# test2235.net
KiCad netlist of a schematic drawn in Altium Designer
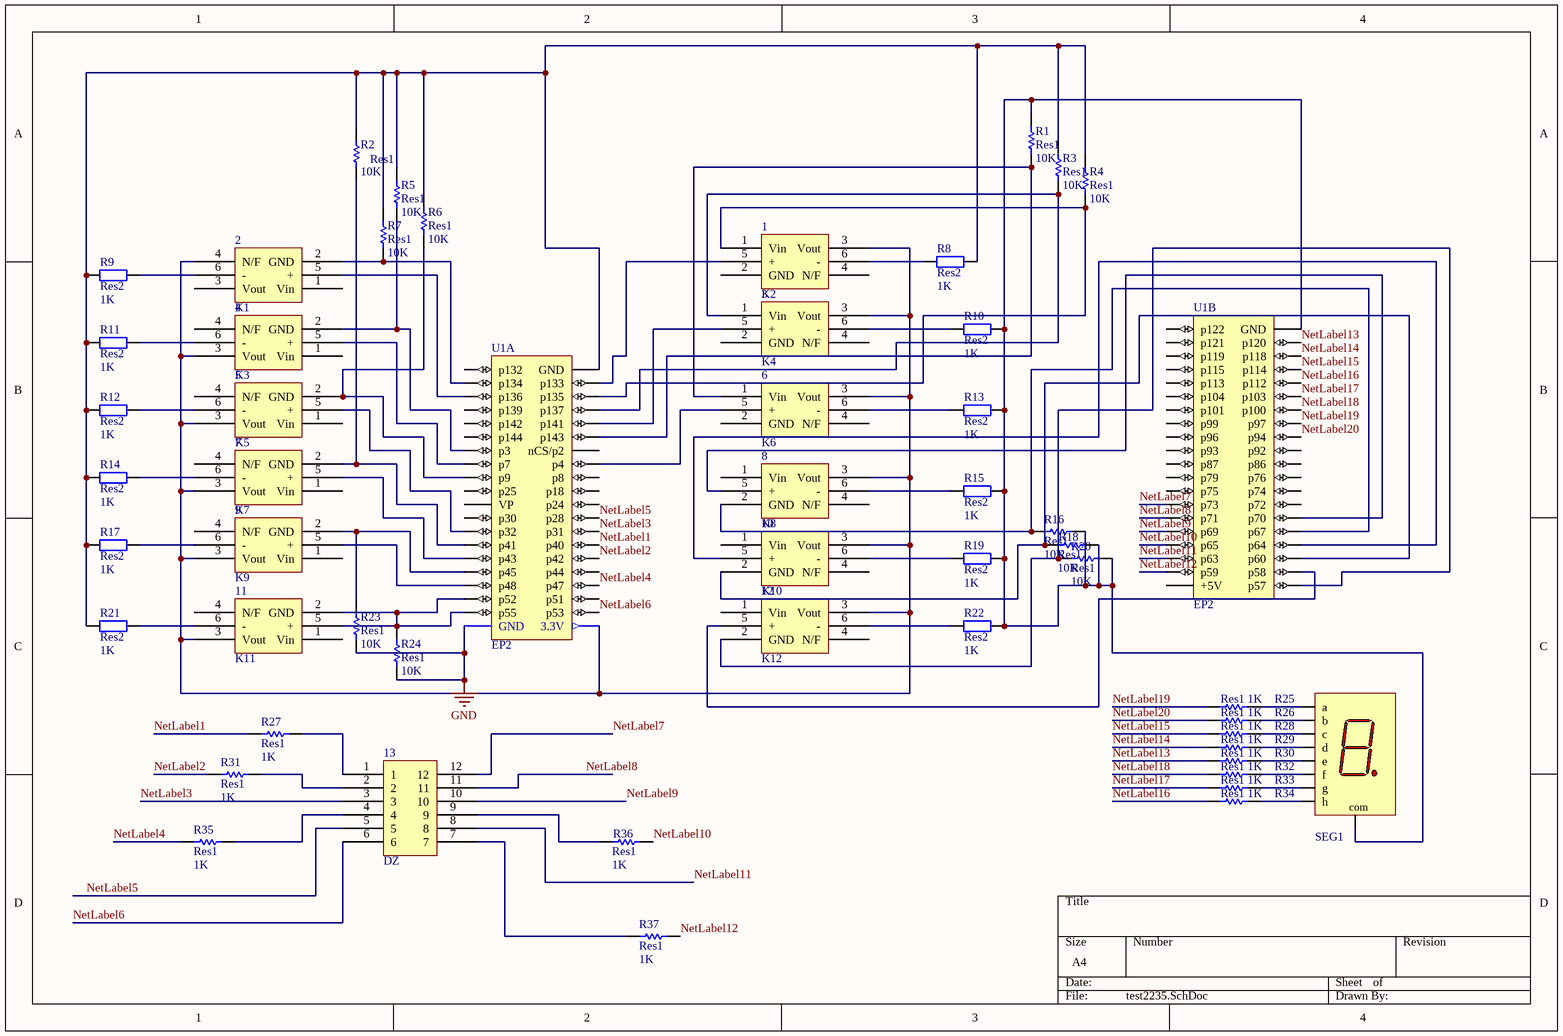
[diagram p0: test2235.SchDoc]

(export (version "E")
  (design (tool "Eeschema 10.0.6"))
  (components
    (comp (ref "1") (value "K2") (footprint "KG") (libsource (lib "KG1") (part "Component_1")))
    (comp (ref "2")
      (value "K1")
      (footprint "KG")
      (libsource (lib "Integrated_Library1") (part "Component_1"))
    )
    (comp (ref "3") (value "K4") (footprint "KG") (libsource (lib "KG1") (part "Component_1")))
    (comp (ref "4")
      (value "K3")
      (footprint "KG")
      (libsource (lib "Integrated_Library1") (part "Component_1"))
    )
    (comp (ref "5")
      (value "K5")
      (footprint "KG")
      (libsource (lib "Integrated_Library1") (part "Component_1"))
    )
    (comp (ref "6") (value "K6") (footprint "KG") (libsource (lib "KG1") (part "Component_1")))
    (comp (ref "7")
      (value "K7")
      (footprint "KG")
      (libsource (lib "Integrated_Library1") (part "Component_1"))
    )
    (comp (ref "8") (value "K8") (footprint "KG") (libsource (lib "KG1") (part "Component_1")))
    (comp (ref "9")
      (value "K9")
      (footprint "KG")
      (libsource (lib "Integrated_Library1") (part "Component_1"))
    )
    (comp (ref "10") (value "K10") (footprint "KG") (libsource (lib "KG1") (part "Component_1")))
    (comp (ref "11")
      (value "K11")
      (footprint "KG")
      (libsource (lib "Integrated_Library1") (part "Component_1"))
    )
    (comp (ref "12") (value "K12") (footprint "KG") (libsource (lib "KG1") (part "Component_1")))
    (comp (ref "13") (value "DZ") (footprint "DZ") (libsource (lib "DZ") (part "DZ")))
    (comp (ref "R1")
      (value "Res1")
      (footprint "AXIAL-0.3")
      (description "Resistor")
      (fields (field (name "ALTIUM_VALUE") "10K") (field (name "PUBLISHER") "Altium Limited"))
      (libsource (lib "Miscellaneous Devices") (part "Res1"))
    )
    (comp (ref "R2")
      (value "Res1")
      (footprint "AXIAL-0.3")
      (description "Resistor")
      (fields (field (name "ALTIUM_VALUE") "10K") (field (name "PUBLISHER") "Altium Limited"))
      (libsource (lib "Miscellaneous Devices") (part "Res1"))
    )
    (comp (ref "R3")
      (value "Res1")
      (footprint "AXIAL-0.3")
      (description "Resistor")
      (fields (field (name "ALTIUM_VALUE") "10K") (field (name "PUBLISHER") "Altium Limited"))
      (libsource (lib "Miscellaneous Devices") (part "Res1"))
    )
    (comp (ref "R4")
      (value "Res1")
      (footprint "AXIAL-0.3")
      (description "Resistor")
      (fields (field (name "ALTIUM_VALUE") "10K") (field (name "PUBLISHER") "Altium Limited"))
      (libsource (lib "Miscellaneous Devices") (part "Res1"))
    )
    (comp (ref "R5")
      (value "Res1")
      (footprint "AXIAL-0.3")
      (description "Resistor")
      (fields (field (name "ALTIUM_VALUE") "10K") (field (name "PUBLISHER") "Altium Limited"))
      (libsource (lib "Miscellaneous Devices") (part "Res1"))
    )
    (comp (ref "R6")
      (value "Res1")
      (footprint "AXIAL-0.3")
      (description "Resistor")
      (fields (field (name "ALTIUM_VALUE") "10K") (field (name "PUBLISHER") "Altium Limited"))
      (libsource (lib "Miscellaneous Devices") (part "Res1"))
    )
    (comp (ref "R7")
      (value "Res1")
      (footprint "AXIAL-0.3")
      (description "Resistor")
      (fields (field (name "ALTIUM_VALUE") "10K") (field (name "PUBLISHER") "Altium Limited"))
      (libsource (lib "Miscellaneous Devices") (part "Res1"))
    )
    (comp (ref "R8")
      (value "Res2")
      (footprint "AXIAL-0.4")
      (description "Resistor")
      (fields (field (name "ALTIUM_VALUE") "1K") (field (name "PUBLISHER") "Altium Limited"))
      (libsource (lib "Miscellaneous Devices") (part "Res2"))
    )
    (comp (ref "R9")
      (value "Res2")
      (footprint "AXIAL-0.4")
      (description "Resistor")
      (fields (field (name "ALTIUM_VALUE") "1K") (field (name "PUBLISHER") "Altium Limited"))
      (libsource (lib "Miscellaneous Devices") (part "Res2"))
    )
    (comp (ref "R10")
      (value "Res2")
      (footprint "AXIAL-0.4")
      (description "Resistor")
      (fields (field (name "ALTIUM_VALUE") "1K") (field (name "PUBLISHER") "Altium Limited"))
      (libsource (lib "Miscellaneous Devices") (part "Res2"))
    )
    (comp (ref "R11")
      (value "Res2")
      (footprint "AXIAL-0.4")
      (description "Resistor")
      (fields (field (name "ALTIUM_VALUE") "1K") (field (name "PUBLISHER") "Altium Limited"))
      (libsource (lib "Miscellaneous Devices") (part "Res2"))
    )
    (comp (ref "R12")
      (value "Res2")
      (footprint "AXIAL-0.4")
      (description "Resistor")
      (fields (field (name "ALTIUM_VALUE") "1K") (field (name "PUBLISHER") "Altium Limited"))
      (libsource (lib "Miscellaneous Devices") (part "Res2"))
    )
    (comp (ref "R13")
      (value "Res2")
      (footprint "AXIAL-0.4")
      (description "Resistor")
      (fields (field (name "ALTIUM_VALUE") "1K") (field (name "PUBLISHER") "Altium Limited"))
      (libsource (lib "Miscellaneous Devices") (part "Res2"))
    )
    (comp (ref "R14")
      (value "Res2")
      (footprint "AXIAL-0.4")
      (description "Resistor")
      (fields (field (name "ALTIUM_VALUE") "1K") (field (name "PUBLISHER") "Altium Limited"))
      (libsource (lib "Miscellaneous Devices") (part "Res2"))
    )
    (comp (ref "R15")
      (value "Res2")
      (footprint "AXIAL-0.4")
      (description "Resistor")
      (fields (field (name "ALTIUM_VALUE") "1K") (field (name "PUBLISHER") "Altium Limited"))
      (libsource (lib "Miscellaneous Devices") (part "Res2"))
    )
    (comp (ref "R16")
      (value "Res1")
      (footprint "AXIAL-0.3")
      (description "Resistor")
      (fields (field (name "ALTIUM_VALUE") "10K") (field (name "PUBLISHER") "Altium Limited"))
      (libsource (lib "Miscellaneous Devices") (part "Res1"))
    )
    (comp (ref "R17")
      (value "Res2")
      (footprint "AXIAL-0.4")
      (description "Resistor")
      (fields (field (name "ALTIUM_VALUE") "1K") (field (name "PUBLISHER") "Altium Limited"))
      (libsource (lib "Miscellaneous Devices") (part "Res2"))
    )
    (comp (ref "R18")
      (value "Res1")
      (footprint "AXIAL-0.3")
      (description "Resistor")
      (fields (field (name "ALTIUM_VALUE") "10K") (field (name "PUBLISHER") "Altium Limited"))
      (libsource (lib "Miscellaneous Devices") (part "Res1"))
    )
    (comp (ref "R19")
      (value "Res2")
      (footprint "AXIAL-0.4")
      (description "Resistor")
      (fields (field (name "ALTIUM_VALUE") "1K") (field (name "PUBLISHER") "Altium Limited"))
      (libsource (lib "Miscellaneous Devices") (part "Res2"))
    )
    (comp (ref "R20")
      (value "Res1")
      (footprint "AXIAL-0.3")
      (description "Resistor")
      (fields (field (name "ALTIUM_VALUE") "10K") (field (name "PUBLISHER") "Altium Limited"))
      (libsource (lib "Miscellaneous Devices") (part "Res1"))
    )
    (comp (ref "R21")
      (value "Res2")
      (footprint "AXIAL-0.4")
      (description "Resistor")
      (fields (field (name "ALTIUM_VALUE") "1K") (field (name "PUBLISHER") "Altium Limited"))
      (libsource (lib "Miscellaneous Devices") (part "Res2"))
    )
    (comp (ref "R22")
      (value "Res2")
      (footprint "AXIAL-0.4")
      (description "Resistor")
      (fields (field (name "ALTIUM_VALUE") "1K") (field (name "PUBLISHER") "Altium Limited"))
      (libsource (lib "Miscellaneous Devices") (part "Res2"))
    )
    (comp (ref "R23")
      (value "Res1")
      (footprint "AXIAL-0.3")
      (description "Resistor")
      (fields (field (name "ALTIUM_VALUE") "10K") (field (name "PUBLISHER") "Altium Limited"))
      (libsource (lib "Miscellaneous Devices") (part "Res1"))
    )
    (comp (ref "R24")
      (value "Res1")
      (footprint "AXIAL-0.3")
      (description "Resistor")
      (fields (field (name "ALTIUM_VALUE") "10K") (field (name "PUBLISHER") "Altium Limited"))
      (libsource (lib "Miscellaneous Devices") (part "Res1"))
    )
    (comp (ref "R25")
      (value "Res1")
      (footprint "AXIAL-0.3")
      (description "Resistor")
      (fields (field (name "ALTIUM_VALUE") "1K") (field (name "PUBLISHER") "Altium Limited"))
      (libsource (lib "Miscellaneous Devices") (part "Res1"))
    )
    (comp (ref "R26")
      (value "Res1")
      (footprint "AXIAL-0.3")
      (description "Resistor")
      (fields (field (name "ALTIUM_VALUE") "1K") (field (name "PUBLISHER") "Altium Limited"))
      (libsource (lib "Miscellaneous Devices") (part "Res1"))
    )
    (comp (ref "R27")
      (value "Res1")
      (footprint "AXIAL-0.3")
      (description "Resistor")
      (fields (field (name "ALTIUM_VALUE") "1K") (field (name "PUBLISHER") "Altium Limited"))
      (libsource (lib "Miscellaneous Devices") (part "Res1"))
    )
    (comp (ref "R28")
      (value "Res1")
      (footprint "AXIAL-0.3")
      (description "Resistor")
      (fields (field (name "ALTIUM_VALUE") "1K") (field (name "PUBLISHER") "Altium Limited"))
      (libsource (lib "Miscellaneous Devices") (part "Res1"))
    )
    (comp (ref "R29")
      (value "Res1")
      (footprint "AXIAL-0.3")
      (description "Resistor")
      (fields (field (name "ALTIUM_VALUE") "1K") (field (name "PUBLISHER") "Altium Limited"))
      (libsource (lib "Miscellaneous Devices") (part "Res1"))
    )
    (comp (ref "R30")
      (value "Res1")
      (footprint "AXIAL-0.3")
      (description "Resistor")
      (fields (field (name "ALTIUM_VALUE") "1K") (field (name "PUBLISHER") "Altium Limited"))
      (libsource (lib "Miscellaneous Devices") (part "Res1"))
    )
    (comp (ref "R31")
      (value "Res1")
      (footprint "AXIAL-0.3")
      (description "Resistor")
      (fields (field (name "ALTIUM_VALUE") "1K") (field (name "PUBLISHER") "Altium Limited"))
      (libsource (lib "Miscellaneous Devices") (part "Res1"))
    )
    (comp (ref "R32")
      (value "Res1")
      (footprint "AXIAL-0.3")
      (description "Resistor")
      (fields (field (name "ALTIUM_VALUE") "1K") (field (name "PUBLISHER") "Altium Limited"))
      (libsource (lib "Miscellaneous Devices") (part "Res1"))
    )
    (comp (ref "R33")
      (value "Res1")
      (footprint "AXIAL-0.3")
      (description "Resistor")
      (fields (field (name "ALTIUM_VALUE") "1K") (field (name "PUBLISHER") "Altium Limited"))
      (libsource (lib "Miscellaneous Devices") (part "Res1"))
    )
    (comp (ref "R34")
      (value "Res1")
      (footprint "AXIAL-0.3")
      (description "Resistor")
      (fields (field (name "ALTIUM_VALUE") "1K") (field (name "PUBLISHER") "Altium Limited"))
      (libsource (lib "Miscellaneous Devices") (part "Res1"))
    )
    (comp (ref "R35")
      (value "Res1")
      (footprint "AXIAL-0.3")
      (description "Resistor")
      (fields (field (name "ALTIUM_VALUE") "1K") (field (name "PUBLISHER") "Altium Limited"))
      (libsource (lib "Miscellaneous Devices") (part "Res1"))
    )
    (comp (ref "R36")
      (value "Res1")
      (footprint "AXIAL-0.3")
      (description "Resistor")
      (fields (field (name "ALTIUM_VALUE") "1K") (field (name "PUBLISHER") "Altium Limited"))
      (libsource (lib "Miscellaneous Devices") (part "Res1"))
    )
    (comp (ref "R37")
      (value "Res1")
      (footprint "AXIAL-0.3")
      (description "Resistor")
      (fields (field (name "ALTIUM_VALUE") "1K") (field (name "PUBLISHER") "Altium Limited"))
      (libsource (lib "Miscellaneous Devices") (part "Res1"))
    )
    (comp (ref "SEG1")
      (value "Displayer-SEG-7")
      (footprint "lanfengdi:QH5011AS")
      (description "七段数码管")
      (libsource (lib "lanfengdi") (part "Displayer-SEG-7"))
    )
    (comp (ref "U1")
      (value "EP2")
      (footprint "lanfengdi:EP2-TQFP144")
      (description "适用于连接西南交大电子学实验室的MFB5上用的FPGA小板")
      (libsource (lib "lanfengdi") (part "EP2"))
    )
  )
  (nets
    (net (code "1") (name "/NetLabel1") (class "Default")
      (node (ref "R27") (pin "2") (pinfunction "2_2") (pintype "passive"))
      (node (ref "U1") (pin "25") (pinfunction "p40_25") (pintype "bidirectional"))
    )
    (net (code "2") (name "/NetLabel2") (class "Default")
      (node (ref "R31") (pin "2") (pinfunction "2_2") (pintype "passive"))
      (node (ref "U1") (pin "24") (pinfunction "p42_24") (pintype "bidirectional"))
    )
    (net (code "3") (name "/NetLabel3") (class "Default")
      (node (ref "13") (pin "3") (pinfunction "3_3") (pintype "passive"))
      (node (ref "U1") (pin "26") (pinfunction "p31_26") (pintype "bidirectional"))
    )
    (net (code "4") (name "/NetLabel4") (class "Default")
      (node (ref "R35") (pin "2") (pinfunction "2_2") (pintype "passive"))
      (node (ref "U1") (pin "22") (pinfunction "p47_22") (pintype "bidirectional"))
    )
    (net (code "5") (name "/NetLabel5") (class "Default")
      (node (ref "13") (pin "5") (pinfunction "5_5") (pintype "passive"))
      (node (ref "U1") (pin "27") (pinfunction "p28_27") (pintype "bidirectional"))
    )
    (net (code "6") (name "/NetLabel6") (class "Default")
      (node (ref "13") (pin "6") (pinfunction "6_6") (pintype "passive"))
      (node (ref "U1") (pin "20") (pinfunction "p53_20") (pintype "bidirectional"))
    )
    (net (code "7") (name "/NetLabel7") (class "Default")
      (node (ref "13") (pin "12") (pinfunction "12_12") (pintype "passive"))
      (node (ref "U1") (pin "52") (pinfunction "p73_52") (pintype "bidirectional"))
    )
    (net (code "8") (name "/NetLabel8") (class "Default")
      (node (ref "13") (pin "11") (pinfunction "11_11") (pintype "passive"))
      (node (ref "U1") (pin "53") (pinfunction "p71_53") (pintype "bidirectional"))
    )
    (net (code "9") (name "/NetLabel9") (class "Default")
      (node (ref "13") (pin "10") (pinfunction "10_10") (pintype "passive"))
      (node (ref "U1") (pin "54") (pinfunction "p69_54") (pintype "bidirectional"))
    )
    (net (code "10") (name "/NetLabel10") (class "Default")
      (node (ref "R36") (pin "1") (pinfunction "1_1") (pintype "passive"))
      (node (ref "U1") (pin "55") (pinfunction "p65_55") (pintype "bidirectional"))
    )
    (net (code "11") (name "/NetLabel11") (class "Default")
      (node (ref "13") (pin "8") (pinfunction "8_8") (pintype "passive"))
      (node (ref "U1") (pin "56") (pinfunction "p63_56") (pintype "bidirectional"))
    )
    (net (code "12") (name "/NetLabel12") (class "Default")
      (node (ref "R37") (pin "1") (pinfunction "1_1") (pintype "passive"))
      (node (ref "U1") (pin "57") (pinfunction "p59_57") (pintype "bidirectional"))
    )
    (net (code "13") (name "/NetLabel13") (class "Default")
      (node (ref "R30") (pin "1") (pinfunction "1_1") (pintype "passive"))
      (node (ref "U1") (pin "77") (pinfunction "p120_77") (pintype "bidirectional"))
    )
    (net (code "14") (name "/NetLabel14") (class "Default")
      (node (ref "R29") (pin "1") (pinfunction "1_1") (pintype "passive"))
      (node (ref "U1") (pin "76") (pinfunction "p118_76") (pintype "bidirectional"))
    )
    (net (code "15") (name "/NetLabel15") (class "Default")
      (node (ref "R28") (pin "1") (pinfunction "1_1") (pintype "passive"))
      (node (ref "U1") (pin "75") (pinfunction "p114_75") (pintype "bidirectional"))
    )
    (net (code "16") (name "/NetLabel16") (class "Default")
      (node (ref "R34") (pin "1") (pinfunction "1_1") (pintype "passive"))
      (node (ref "U1") (pin "74") (pinfunction "p112_74") (pintype "bidirectional"))
    )
    (net (code "17") (name "/NetLabel17") (class "Default")
      (node (ref "R33") (pin "1") (pinfunction "1_1") (pintype "passive"))
      (node (ref "U1") (pin "73") (pinfunction "p103_73") (pintype "bidirectional"))
    )
    (net (code "18") (name "/NetLabel18") (class "Default")
      (node (ref "R32") (pin "1") (pinfunction "1_1") (pintype "passive"))
      (node (ref "U1") (pin "72") (pinfunction "p100_72") (pintype "bidirectional"))
    )
    (net (code "19") (name "/NetLabel19") (class "Default")
      (node (ref "R25") (pin "1") (pinfunction "1_1") (pintype "passive"))
      (node (ref "U1") (pin "71") (pinfunction "p97_71") (pintype "bidirectional"))
    )
    (net (code "20") (name "/NetLabel20") (class "Default")
      (node (ref "R26") (pin "1") (pinfunction "1_1") (pintype "passive"))
      (node (ref "U1") (pin "70") (pinfunction "p94_70") (pintype "bidirectional"))
    )
    (net (code "21") (name "GND") (class "Default")
      (node (ref "R23") (pin "1") (pinfunction "1_1") (pintype "passive"))
      (node (ref "R24") (pin "1") (pinfunction "1_1") (pintype "passive"))
      (node (ref "U1") (pin "79") (pinfunction "GND_79") (pintype "power_in"))
    )
    (net (code "22") (name "Net-(1-+)") (class "Default")
      (node (ref "1") (pin "5") (pinfunction "+_5") (pintype "passive"))
      (node (ref "U1") (pin "37") (pinfunction "p133_37") (pintype "bidirectional"))
    )
    (net (code "23") (name "Net-(1--)") (class "Default")
      (node (ref "1") (pin "6") (pinfunction "-_6") (pintype "passive"))
      (node (ref "R8") (pin "1") (pinfunction "1_1") (pintype "passive"))
    )
    (net (code "24") (name "Net-(1-Vin)") (class "Default")
      (node (ref "1") (pin "1") (pinfunction "Vin_1") (pintype "passive"))
      (node (ref "R4") (pin "1") (pinfunction "1_1") (pintype "passive"))
      (node (ref "U1") (pin "36") (pinfunction "p135_36") (pintype "bidirectional"))
    )
    (net (code "25") (name "Net-(1-Vout)") (class "Default")
      (node (ref "1") (pin "3") (pinfunction "Vout_3") (pintype "passive"))
      (node (ref "10") (pin "3") (pinfunction "Vout_3") (pintype "passive"))
      (node (ref "11") (pin "3") (pinfunction "Vout_3") (pintype "passive"))
      (node (ref "12") (pin "3") (pinfunction "Vout_3") (pintype "passive"))
      (node (ref "2") (pin "4") (pinfunction "N/F_4") (pintype "passive"))
      (node (ref "3") (pin "3") (pinfunction "Vout_3") (pintype "passive"))
      (node (ref "4") (pin "3") (pinfunction "Vout_3") (pintype "passive"))
      (node (ref "5") (pin "3") (pinfunction "Vout_3") (pintype "passive"))
      (node (ref "6") (pin "3") (pinfunction "Vout_3") (pintype "passive"))
      (node (ref "7") (pin "3") (pinfunction "Vout_3") (pintype "passive"))
      (node (ref "8") (pin "3") (pinfunction "Vout_3") (pintype "passive"))
      (node (ref "9") (pin "3") (pinfunction "Vout_3") (pintype "passive"))
      (node (ref "U1") (pin "80") (pinfunction "3.3V_80") (pintype "output"))
    )
    (net (code "26") (name "Net-(2-+)") (class "Default")
      (node (ref "2") (pin "5") (pinfunction "+_5") (pintype "passive"))
      (node (ref "U1") (pin "3") (pinfunction "p136_3") (pintype "bidirectional"))
    )
    (net (code "27") (name "Net-(2--)") (class "Default")
      (node (ref "2") (pin "6") (pinfunction "-_6") (pintype "passive"))
      (node (ref "R9") (pin "2") (pinfunction "2_2") (pintype "passive"))
    )
    (net (code "28") (name "Net-(2-GND)") (class "Default")
      (node (ref "2") (pin "2") (pinfunction "GND_2") (pintype "passive"))
      (node (ref "R7") (pin "1") (pinfunction "1_1") (pintype "passive"))
      (node (ref "U1") (pin "2") (pinfunction "p134_2") (pintype "bidirectional"))
    )
    (net (code "29") (name "Net-(3-+)") (class "Default")
      (node (ref "3") (pin "5") (pinfunction "+_5") (pintype "passive"))
      (node (ref "U1") (pin "34") (pinfunction "p141_34") (pintype "bidirectional"))
    )
    (net (code "30") (name "Net-(3--)") (class "Default")
      (node (ref "3") (pin "6") (pinfunction "-_6") (pintype "passive"))
      (node (ref "R10") (pin "1") (pinfunction "1_1") (pintype "passive"))
    )
    (net (code "31") (name "Net-(3-Vin)") (class "Default")
      (node (ref "3") (pin "1") (pinfunction "Vin_1") (pintype "passive"))
      (node (ref "R3") (pin "1") (pinfunction "1_1") (pintype "passive"))
      (node (ref "U1") (pin "35") (pinfunction "p137_35") (pintype "bidirectional"))
    )
    (net (code "32") (name "Net-(4-+)") (class "Default")
      (node (ref "4") (pin "5") (pinfunction "+_5") (pintype "passive"))
      (node (ref "U1") (pin "8") (pinfunction "p7_8") (pintype "bidirectional"))
    )
    (net (code "33") (name "Net-(4--)") (class "Default")
      (node (ref "4") (pin "6") (pinfunction "-_6") (pintype "passive"))
      (node (ref "R11") (pin "2") (pinfunction "2_2") (pintype "passive"))
    )
    (net (code "34") (name "Net-(4-GND)") (class "Default")
      (node (ref "4") (pin "2") (pinfunction "GND_2") (pintype "passive"))
      (node (ref "R5") (pin "1") (pinfunction "1_1") (pintype "passive"))
      (node (ref "U1") (pin "7") (pinfunction "p3_7") (pintype "bidirectional"))
    )
    (net (code "35") (name "Net-(5-+)") (class "Default")
      (node (ref "5") (pin "5") (pinfunction "+_5") (pintype "passive"))
      (node (ref "U1") (pin "13") (pinfunction "p32_13") (pintype "bidirectional"))
    )
    (net (code "36") (name "Net-(5--)") (class "Default")
      (node (ref "5") (pin "6") (pinfunction "-_6") (pintype "passive"))
      (node (ref "R12") (pin "2") (pinfunction "2_2") (pintype "passive"))
    )
    (net (code "37") (name "Net-(5-GND)") (class "Default")
      (node (ref "5") (pin "2") (pinfunction "GND_2") (pintype "passive"))
      (node (ref "R6") (pin "1") (pinfunction "1_1") (pintype "passive"))
      (node (ref "U1") (pin "9") (pinfunction "p9_9") (pintype "bidirectional"))
    )
    (net (code "38") (name "Net-(6-+)") (class "Default")
      (node (ref "6") (pin "5") (pinfunction "+_5") (pintype "passive"))
      (node (ref "U1") (pin "31") (pinfunction "p4_31") (pintype "bidirectional"))
    )
    (net (code "39") (name "Net-(6--)") (class "Default")
      (node (ref "6") (pin "6") (pinfunction "-_6") (pintype "passive"))
      (node (ref "R13") (pin "1") (pinfunction "1_1") (pintype "passive"))
    )
    (net (code "40") (name "Net-(6-Vin)") (class "Default")
      (node (ref "6") (pin "1") (pinfunction "Vin_1") (pintype "passive"))
      (node (ref "R1") (pin "1") (pinfunction "1_1") (pintype "passive"))
      (node (ref "U1") (pin "33") (pinfunction "p143_33") (pintype "bidirectional"))
    )
    (net (code "41") (name "Net-(7-+)") (class "Default")
      (node (ref "7") (pin "5") (pinfunction "+_5") (pintype "passive"))
      (node (ref "U1") (pin "15") (pinfunction "p43_15") (pintype "bidirectional"))
    )
    (net (code "42") (name "Net-(7--)") (class "Default")
      (node (ref "7") (pin "6") (pinfunction "-_6") (pintype "passive"))
      (node (ref "R14") (pin "2") (pinfunction "2_2") (pintype "passive"))
    )
    (net (code "43") (name "Net-(7-GND)") (class "Default")
      (node (ref "7") (pin "2") (pinfunction "GND_2") (pintype "passive"))
      (node (ref "R2") (pin "1") (pinfunction "1_1") (pintype "passive"))
      (node (ref "U1") (pin "14") (pinfunction "p41_14") (pintype "bidirectional"))
    )
    (net (code "44") (name "Net-(8-+)") (class "Default")
      (node (ref "8") (pin "5") (pinfunction "+_5") (pintype "passive"))
      (node (ref "U1") (pin "64") (pinfunction "p70_64") (pintype "bidirectional"))
    )
    (net (code "45") (name "Net-(8--)") (class "Default")
      (node (ref "8") (pin "6") (pinfunction "-_6") (pintype "passive"))
      (node (ref "R15") (pin "1") (pinfunction "1_1") (pintype "passive"))
    )
    (net (code "46") (name "Net-(8-GND)") (class "Default")
      (node (ref "8") (pin "2") (pinfunction "GND_2") (pintype "passive"))
      (node (ref "R16") (pin "1") (pinfunction "1_1") (pintype "passive"))
      (node (ref "U1") (pin "63") (pinfunction "p67_63") (pintype "bidirectional"))
    )
    (net (code "47") (name "Net-(9-+)") (class "Default")
      (node (ref "9") (pin "5") (pinfunction "+_5") (pintype "passive"))
      (node (ref "U1") (pin "17") (pinfunction "p48_17") (pintype "bidirectional"))
    )
    (net (code "48") (name "Net-(9--)") (class "Default")
      (node (ref "9") (pin "6") (pinfunction "-_6") (pintype "passive"))
      (node (ref "R17") (pin "2") (pinfunction "2_2") (pintype "passive"))
    )
    (net (code "49") (name "Net-(9-GND)") (class "Default")
      (node (ref "9") (pin "2") (pinfunction "GND_2") (pintype "passive"))
      (node (ref "R23") (pin "2") (pinfunction "2_2") (pintype "passive"))
      (node (ref "U1") (pin "16") (pinfunction "p45_16") (pintype "bidirectional"))
    )
    (net (code "50") (name "Net-(10-+)") (class "Default")
      (node (ref "10") (pin "5") (pinfunction "+_5") (pintype "passive"))
      (node (ref "U1") (pin "62") (pinfunction "p64_62") (pintype "bidirectional"))
    )
    (net (code "51") (name "Net-(10--)") (class "Default")
      (node (ref "10") (pin "6") (pinfunction "-_6") (pintype "passive"))
      (node (ref "R19") (pin "1") (pinfunction "1_1") (pintype "passive"))
    )
    (net (code "52") (name "Net-(10-GND)") (class "Default")
      (node (ref "10") (pin "2") (pinfunction "GND_2") (pintype "passive"))
      (node (ref "R18") (pin "1") (pinfunction "1_1") (pintype "passive"))
      (node (ref "U1") (pin "61") (pinfunction "p60_61") (pintype "bidirectional"))
    )
    (net (code "53") (name "Net-(11-+)") (class "Default")
      (node (ref "11") (pin "2") (pinfunction "GND_2") (pintype "passive"))
      (node (ref "11") (pin "5") (pinfunction "+_5") (pintype "passive"))
      (node (ref "R24") (pin "2") (pinfunction "2_2") (pintype "passive"))
      (node (ref "U1") (pin "18") (pinfunction "p52_18") (pintype "bidirectional"))
      (node (ref "U1") (pin "19") (pinfunction "p55_19") (pintype "bidirectional"))
    )
    (net (code "54") (name "Net-(11--)") (class "Default")
      (node (ref "11") (pin "6") (pinfunction "-_6") (pintype "passive"))
      (node (ref "R21") (pin "2") (pinfunction "2_2") (pintype "passive"))
    )
    (net (code "55") (name "Net-(12-+)") (class "Default")
      (node (ref "12") (pin "5") (pinfunction "+_5") (pintype "passive"))
      (node (ref "U1") (pin "60") (pinfunction "p58_60") (pintype "bidirectional"))
    )
    (net (code "56") (name "Net-(12--)") (class "Default")
      (node (ref "12") (pin "6") (pinfunction "-_6") (pintype "passive"))
      (node (ref "R22") (pin "1") (pinfunction "1_1") (pintype "passive"))
    )
    (net (code "57") (name "Net-(12-GND)") (class "Default")
      (node (ref "12") (pin "2") (pinfunction "GND_2") (pintype "passive"))
      (node (ref "R20") (pin "1") (pinfunction "1_1") (pintype "passive"))
      (node (ref "U1") (pin "59") (pinfunction "p57_59") (pintype "bidirectional"))
    )
    (net (code "58") (name "Net-(13-Pad1)") (class "Default")
      (node (ref "13") (pin "1") (pinfunction "1_1") (pintype "passive"))
      (node (ref "R27") (pin "1") (pinfunction "1_1") (pintype "passive"))
    )
    (net (code "59") (name "Net-(13-Pad2)") (class "Default")
      (node (ref "13") (pin "2") (pinfunction "2_2") (pintype "passive"))
      (node (ref "R31") (pin "1") (pinfunction "1_1") (pintype "passive"))
    )
    (net (code "60") (name "Net-(13-Pad4)") (class "Default")
      (node (ref "13") (pin "4") (pinfunction "4_4") (pintype "passive"))
      (node (ref "R35") (pin "1") (pinfunction "1_1") (pintype "passive"))
    )
    (net (code "61") (name "Net-(13-Pad7)") (class "Default")
      (node (ref "13") (pin "7") (pinfunction "7_7") (pintype "passive"))
      (node (ref "R37") (pin "2") (pinfunction "2_2") (pintype "passive"))
    )
    (net (code "62") (name "Net-(13-Pad9)") (class "Default")
      (node (ref "13") (pin "9") (pinfunction "9_9") (pintype "passive"))
      (node (ref "R36") (pin "2") (pinfunction "2_2") (pintype "passive"))
    )
    (net (code "63") (name "Net-(R11-Pad1)") (class "Default")
      (node (ref "R11") (pin "1") (pinfunction "1_1") (pintype "passive"))
      (node (ref "R12") (pin "1") (pinfunction "1_1") (pintype "passive"))
      (node (ref "R14") (pin "1") (pinfunction "1_1") (pintype "passive"))
      (node (ref "R17") (pin "1") (pinfunction "1_1") (pintype "passive"))
      (node (ref "R2") (pin "2") (pinfunction "2_2") (pintype "passive"))
      (node (ref "R21") (pin "1") (pinfunction "1_1") (pintype "passive"))
      (node (ref "R3") (pin "2") (pinfunction "2_2") (pintype "passive"))
      (node (ref "R4") (pin "2") (pinfunction "2_2") (pintype "passive"))
      (node (ref "R5") (pin "2") (pinfunction "2_2") (pintype "passive"))
      (node (ref "R6") (pin "2") (pinfunction "2_2") (pintype "passive"))
      (node (ref "R7") (pin "2") (pinfunction "2_2") (pintype "passive"))
      (node (ref "R8") (pin "2") (pinfunction "2_2") (pintype "passive"))
      (node (ref "R9") (pin "1") (pinfunction "1_1") (pintype "passive"))
      (node (ref "U1") (pin "38") (pinfunction "GND_38") (pintype "passive"))
    )
    (net (code "64") (name "Net-(R25-Pad2)") (class "Default")
      (node (ref "R25") (pin "2") (pinfunction "2_2") (pintype "passive"))
      (node (ref "SEG1") (pin "a") (pinfunction "a_a") (pintype "passive"))
    )
    (net (code "65") (name "Net-(R26-Pad2)") (class "Default")
      (node (ref "R26") (pin "2") (pinfunction "2_2") (pintype "passive"))
      (node (ref "SEG1") (pin "b") (pinfunction "b_b") (pintype "passive"))
    )
    (net (code "66") (name "Net-(R28-Pad2)") (class "Default")
      (node (ref "R28") (pin "2") (pinfunction "2_2") (pintype "passive"))
      (node (ref "SEG1") (pin "c") (pinfunction "c_c") (pintype "passive"))
    )
    (net (code "67") (name "Net-(R29-Pad2)") (class "Default")
      (node (ref "R29") (pin "2") (pinfunction "2_2") (pintype "passive"))
      (node (ref "SEG1") (pin "d") (pinfunction "d_d") (pintype "passive"))
    )
    (net (code "68") (name "Net-(R30-Pad2)") (class "Default")
      (node (ref "R30") (pin "2") (pinfunction "2_2") (pintype "passive"))
      (node (ref "SEG1") (pin "e") (pinfunction "e_e") (pintype "passive"))
    )
    (net (code "69") (name "Net-(R32-Pad2)") (class "Default")
      (node (ref "R32") (pin "2") (pinfunction "2_2") (pintype "passive"))
      (node (ref "SEG1") (pin "f") (pinfunction "f_f") (pintype "passive"))
    )
    (net (code "70") (name "Net-(R33-Pad2)") (class "Default")
      (node (ref "R33") (pin "2") (pinfunction "2_2") (pintype "passive"))
      (node (ref "SEG1") (pin "g") (pinfunction "g_g") (pintype "passive"))
    )
    (net (code "71") (name "Net-(R34-Pad2)") (class "Default")
      (node (ref "R34") (pin "2") (pinfunction "2_2") (pintype "passive"))
      (node (ref "SEG1") (pin "h") (pinfunction "h_h") (pintype "passive"))
    )
    (net (code "72") (name "Net-(U1B-GND)") (class "Default")
      (node (ref "R1") (pin "2") (pinfunction "2_2") (pintype "passive"))
      (node (ref "R10") (pin "2") (pinfunction "2_2") (pintype "passive"))
      (node (ref "R13") (pin "2") (pinfunction "2_2") (pintype "passive"))
      (node (ref "R15") (pin "2") (pinfunction "2_2") (pintype "passive"))
      (node (ref "R16") (pin "2") (pinfunction "2_2") (pintype "passive"))
      (node (ref "R18") (pin "2") (pinfunction "2_2") (pintype "passive"))
      (node (ref "R19") (pin "2") (pinfunction "2_2") (pintype "passive"))
      (node (ref "R20") (pin "2") (pinfunction "2_2") (pintype "passive"))
      (node (ref "R22") (pin "2") (pinfunction "2_2") (pintype "passive"))
      (node (ref "SEG1") (pin "com") (pinfunction "com_com") (pintype "passive"))
      (node (ref "U1") (pin "78") (pinfunction "GND_78") (pintype "passive"))
    )
    (net (code "73") (name "unconnected-(1-GND-Pad2)") (class "Default")
      (node (ref "1") (pin "2") (pinfunction "GND_2") (pintype "passive"))
    )
    (net (code "74") (name "unconnected-(1-N{slash}F-Pad4)") (class "Default")
      (node (ref "1") (pin "4") (pinfunction "N/F_4") (pintype "passive"))
    )
    (net (code "75") (name "unconnected-(2-Vin-Pad1)") (class "Default")
      (node (ref "2") (pin "1") (pinfunction "Vin_1") (pintype "passive"))
    )
    (net (code "76") (name "unconnected-(2-Vout-Pad3)") (class "Default")
      (node (ref "2") (pin "3") (pinfunction "Vout_3") (pintype "passive"))
    )
    (net (code "77") (name "unconnected-(3-GND-Pad2)") (class "Default")
      (node (ref "3") (pin "2") (pinfunction "GND_2") (pintype "passive"))
    )
    (net (code "78") (name "unconnected-(3-N{slash}F-Pad4)") (class "Default")
      (node (ref "3") (pin "4") (pinfunction "N/F_4") (pintype "passive"))
    )
    (net (code "79") (name "unconnected-(4-N{slash}F-Pad4)") (class "Default")
      (node (ref "4") (pin "4") (pinfunction "N/F_4") (pintype "passive"))
    )
    (net (code "80") (name "unconnected-(4-Vin-Pad1)") (class "Default")
      (node (ref "4") (pin "1") (pinfunction "Vin_1") (pintype "passive"))
    )
    (net (code "81") (name "unconnected-(5-N{slash}F-Pad4)") (class "Default")
      (node (ref "5") (pin "4") (pinfunction "N/F_4") (pintype "passive"))
    )
    (net (code "82") (name "unconnected-(5-Vin-Pad1)") (class "Default")
      (node (ref "5") (pin "1") (pinfunction "Vin_1") (pintype "passive"))
    )
    (net (code "83") (name "unconnected-(6-GND-Pad2)") (class "Default")
      (node (ref "6") (pin "2") (pinfunction "GND_2") (pintype "passive"))
    )
    (net (code "84") (name "unconnected-(6-N{slash}F-Pad4)") (class "Default")
      (node (ref "6") (pin "4") (pinfunction "N/F_4") (pintype "passive"))
    )
    (net (code "85") (name "unconnected-(7-N{slash}F-Pad4)") (class "Default")
      (node (ref "7") (pin "4") (pinfunction "N/F_4") (pintype "passive"))
    )
    (net (code "86") (name "unconnected-(7-Vin-Pad1)") (class "Default")
      (node (ref "7") (pin "1") (pinfunction "Vin_1") (pintype "passive"))
    )
    (net (code "87") (name "unconnected-(8-N{slash}F-Pad4)") (class "Default")
      (node (ref "8") (pin "4") (pinfunction "N/F_4") (pintype "passive"))
    )
    (net (code "88") (name "unconnected-(8-Vin-Pad1)") (class "Default")
      (node (ref "8") (pin "1") (pinfunction "Vin_1") (pintype "passive"))
    )
    (net (code "89") (name "unconnected-(9-N{slash}F-Pad4)") (class "Default")
      (node (ref "9") (pin "4") (pinfunction "N/F_4") (pintype "passive"))
    )
    (net (code "90") (name "unconnected-(9-Vin-Pad1)") (class "Default")
      (node (ref "9") (pin "1") (pinfunction "Vin_1") (pintype "passive"))
    )
    (net (code "91") (name "unconnected-(10-N{slash}F-Pad4)") (class "Default")
      (node (ref "10") (pin "4") (pinfunction "N/F_4") (pintype "passive"))
    )
    (net (code "92") (name "unconnected-(10-Vin-Pad1)") (class "Default")
      (node (ref "10") (pin "1") (pinfunction "Vin_1") (pintype "passive"))
    )
    (net (code "93") (name "unconnected-(11-N{slash}F-Pad4)") (class "Default")
      (node (ref "11") (pin "4") (pinfunction "N/F_4") (pintype "passive"))
    )
    (net (code "94") (name "unconnected-(11-Vin-Pad1)") (class "Default")
      (node (ref "11") (pin "1") (pinfunction "Vin_1") (pintype "passive"))
    )
    (net (code "95") (name "unconnected-(12-N{slash}F-Pad4)") (class "Default")
      (node (ref "12") (pin "4") (pinfunction "N/F_4") (pintype "passive"))
    )
    (net (code "96") (name "unconnected-(12-Vin-Pad1)") (class "Default")
      (node (ref "12") (pin "1") (pinfunction "Vin_1") (pintype "passive"))
    )
    (net (code "97") (name "unconnected-(U1A-VP-Pad11)") (class "Default")
      (node (ref "U1") (pin "11") (pinfunction "VP_11") (pintype "power_in"))
    )
    (net (code "98") (name "unconnected-(U1A-nCS{slash}p2-Pad32)") (class "Default")
      (node (ref "U1") (pin "32") (pinfunction "nCS/p2_32") (pintype "passive"))
    )
    (net (code "99") (name "unconnected-(U1A-p8-Pad30)") (class "Default")
      (node (ref "U1") (pin "30") (pinfunction "p8_30") (pintype "bidirectional"))
    )
    (net (code "100") (name "unconnected-(U1A-p18-Pad29)") (class "Default")
      (node (ref "U1") (pin "29") (pinfunction "p18_29") (pintype "bidirectional"))
    )
    (net (code "101") (name "unconnected-(U1A-p24-Pad28)") (class "Default")
      (node (ref "U1") (pin "28") (pinfunction "p24_28") (pintype "bidirectional"))
    )
    (net (code "102") (name "unconnected-(U1A-p25-Pad10)") (class "Default")
      (node (ref "U1") (pin "10") (pinfunction "p25_10") (pintype "bidirectional"))
    )
    (net (code "103") (name "unconnected-(U1A-p30-Pad12)") (class "Default")
      (node (ref "U1") (pin "12") (pinfunction "p30_12") (pintype "bidirectional"))
    )
    (net (code "104") (name "unconnected-(U1A-p44-Pad23)") (class "Default")
      (node (ref "U1") (pin "23") (pinfunction "p44_23") (pintype "bidirectional"))
    )
    (net (code "105") (name "unconnected-(U1A-p51-Pad21)") (class "Default")
      (node (ref "U1") (pin "21") (pinfunction "p51_21") (pintype "bidirectional"))
    )
    (net (code "106") (name "unconnected-(U1A-p132-Pad1)") (class "Default")
      (node (ref "U1") (pin "1") (pinfunction "p132_1") (pintype "bidirectional"))
    )
    (net (code "107") (name "unconnected-(U1A-p139-Pad4)") (class "Default")
      (node (ref "U1") (pin "4") (pinfunction "p139_4") (pintype "bidirectional"))
    )
    (net (code "108") (name "unconnected-(U1A-p142-Pad5)") (class "Default")
      (node (ref "U1") (pin "5") (pinfunction "p142_5") (pintype "bidirectional"))
    )
    (net (code "109") (name "unconnected-(U1A-p144-Pad6)") (class "Default")
      (node (ref "U1") (pin "6") (pinfunction "p144_6") (pintype "bidirectional"))
    )
    (net (code "110") (name "unconnected-(U1B-+5V-Pad58)") (class "Default")
      (node (ref "U1") (pin "58") (pinfunction "+5V_58") (pintype "passive"))
    )
    (net (code "111") (name "unconnected-(U1B-p72-Pad65)") (class "Default")
      (node (ref "U1") (pin "65") (pinfunction "p72_65") (pintype "bidirectional"))
    )
    (net (code "112") (name "unconnected-(U1B-p74-Pad66)") (class "Default")
      (node (ref "U1") (pin "66") (pinfunction "p74_66") (pintype "bidirectional"))
    )
    (net (code "113") (name "unconnected-(U1B-p75-Pad51)") (class "Default")
      (node (ref "U1") (pin "51") (pinfunction "p75_51") (pintype "bidirectional"))
    )
    (net (code "114") (name "unconnected-(U1B-p76-Pad67)") (class "Default")
      (node (ref "U1") (pin "67") (pinfunction "p76_67") (pintype "bidirectional"))
    )
    (net (code "115") (name "unconnected-(U1B-p79-Pad50)") (class "Default")
      (node (ref "U1") (pin "50") (pinfunction "p79_50") (pintype "bidirectional"))
    )
    (net (code "116") (name "unconnected-(U1B-p86-Pad68)") (class "Default")
      (node (ref "U1") (pin "68") (pinfunction "p86_68") (pintype "bidirectional"))
    )
    (net (code "117") (name "unconnected-(U1B-p87-Pad49)") (class "Default")
      (node (ref "U1") (pin "49") (pinfunction "p87_49") (pintype "bidirectional"))
    )
    (net (code "118") (name "unconnected-(U1B-p92-Pad69)") (class "Default")
      (node (ref "U1") (pin "69") (pinfunction "p92_69") (pintype "bidirectional"))
    )
    (net (code "119") (name "unconnected-(U1B-p93-Pad48)") (class "Default")
      (node (ref "U1") (pin "48") (pinfunction "p93_48") (pintype "bidirectional"))
    )
    (net (code "120") (name "unconnected-(U1B-p96-Pad47)") (class "Default")
      (node (ref "U1") (pin "47") (pinfunction "p96_47") (pintype "bidirectional"))
    )
    (net (code "121") (name "unconnected-(U1B-p99-Pad46)") (class "Default")
      (node (ref "U1") (pin "46") (pinfunction "p99_46") (pintype "bidirectional"))
    )
    (net (code "122") (name "unconnected-(U1B-p101-Pad45)") (class "Default")
      (node (ref "U1") (pin "45") (pinfunction "p101_45") (pintype "bidirectional"))
    )
    (net (code "123") (name "unconnected-(U1B-p104-Pad44)") (class "Default")
      (node (ref "U1") (pin "44") (pinfunction "p104_44") (pintype "bidirectional"))
    )
    (net (code "124") (name "unconnected-(U1B-p113-Pad43)") (class "Default")
      (node (ref "U1") (pin "43") (pinfunction "p113_43") (pintype "bidirectional"))
    )
    (net (code "125") (name "unconnected-(U1B-p115-Pad42)") (class "Default")
      (node (ref "U1") (pin "42") (pinfunction "p115_42") (pintype "bidirectional"))
    )
    (net (code "126") (name "unconnected-(U1B-p119-Pad41)") (class "Default")
      (node (ref "U1") (pin "41") (pinfunction "p119_41") (pintype "bidirectional"))
    )
    (net (code "127") (name "unconnected-(U1B-p121-Pad40)") (class "Default")
      (node (ref "U1") (pin "40") (pinfunction "p121_40") (pintype "bidirectional"))
    )
    (net (code "128") (name "unconnected-(U1B-p122-Pad39)") (class "Default")
      (node (ref "U1") (pin "39") (pinfunction "p122_39") (pintype "bidirectional"))
    )
  )
)
